# 04_DCDC_3V3.net
KiCad netlist of a schematic drawn in Altium Designer
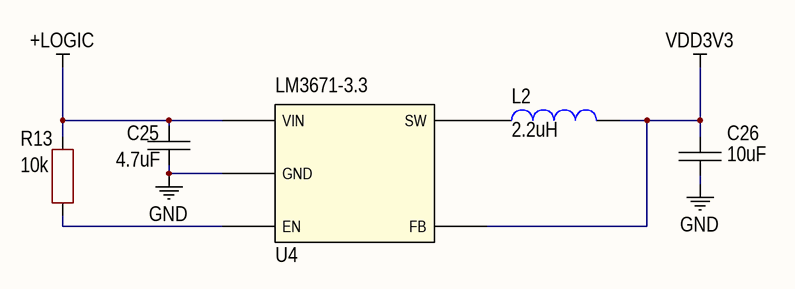
[diagram p0: 04_DCDC_3V3.SchDoc]

(export (version "E")
  (design (tool "Eeschema 10.0.6"))
  (components
    (comp (ref "C25")
      (value "4.7uF")
      (footprint "CAP: 0805")
      (fields
        (field (name "MANUFACTURER") "Yageo")
        (field (name "PARTNUMBER") "CC0805KRX7R7BB104")
        (field (name "VALUEMANUFACTURERPARTNUMBER") "Ceramic capacitor, 4.7uF, X7R, ±10%, 16V, 0805, -55...+125°C")
      )
      (libsource (lib "capacitor") (part "Ceramic_0805"))
    )
    (comp (ref "C26")
      (value "10uF")
      (footprint "CAP: 0805")
      (fields
        (field (name "MANUFACTURER") "Yageo")
        (field (name "PARTNUMBER") "CC0805KRX7R7BB104")
        (field (name "VALUEMANUFACTURERPARTNUMBER") "Ceramic capacitor, 10uF, X7R, ±10%, 16V, 0805, -55...+125°C")
      )
      (libsource (lib "capacitor") (part "Ceramic_0805"))
    )
    (comp (ref "L2")
      (value "2.2uH")
      (footprint "IND: SDR0805")
      (fields
        (field (name "MANUFACTURER") "Bourns")
        (field (name "PARTNUMBER") "SDR0805-4R7ML")
        (field (name "VALUEMANUFACTURERPARTNUMBER") "Fixed inductor, 2.2uH, ±20%, SDR0805, 3.7A, -40...+125°C")
      )
      (libsource (lib "inductor") (part "Inductor_SDR0805"))
    )
    (comp (ref "R13")
      (value "10k")
      (footprint "RES: 0603")
      (fields
        (field (name "MANUFACTURER") "Yageo")
        (field (name "PARTNUMBER") "RC0603JR-07100RL")
        (field (name "VALUEMANUFACTURERPARTNUMBER") "Resistor film, 10k, ±5%, 0603, 0.1W, -55...+125°C")
      )
      (libsource (lib "resistor") (part "Resistor_0603"))
    )
    (comp (ref "U4")
      (value "LM3671-3.3")
      (footprint "SOT23-5")
      (fields (field (name "MANUFACTURER") "Texas Instruments"))
      (libsource (lib "MyLib") (part "LM3671-3.3"))
    )
  )
  (nets
    (net (code "1") (name "+LOGIC") (class "Default")
      (node (ref "C25") (pin "2") (pinfunction "2_2") (pintype "passive"))
      (node (ref "R13") (pin "2") (pinfunction "2_2") (pintype "passive"))
      (node (ref "U4") (pin "1") (pinfunction "VIN_1") (pintype "passive"))
    )
    (net (code "2") (name "GND") (class "Default")
      (node (ref "C25") (pin "1") (pinfunction "1_1") (pintype "passive"))
      (node (ref "C26") (pin "1") (pinfunction "1_1") (pintype "passive"))
      (node (ref "U4") (pin "2") (pinfunction "GND_2") (pintype "passive"))
    )
    (net (code "3") (name "Net-(U4-EN)") (class "Default")
      (node (ref "R13") (pin "1") (pinfunction "1_1") (pintype "passive"))
      (node (ref "U4") (pin "3") (pinfunction "EN_3") (pintype "passive"))
    )
    (net (code "4") (name "Net-(U4-SW)") (class "Default")
      (node (ref "L2") (pin "2") (pinfunction "2_2") (pintype "passive"))
      (node (ref "U4") (pin "5") (pinfunction "SW_5") (pintype "passive"))
    )
    (net (code "5") (name "VDD3V3") (class "Default")
      (node (ref "C26") (pin "2") (pinfunction "2_2") (pintype "passive"))
      (node (ref "L2") (pin "1") (pinfunction "1_1") (pintype "passive"))
      (node (ref "U4") (pin "4") (pinfunction "FB_4") (pintype "passive"))
    )
  )
)
